# simple_motor_driver.net
KiCad netlist of a schematic drawn in Altium Designer
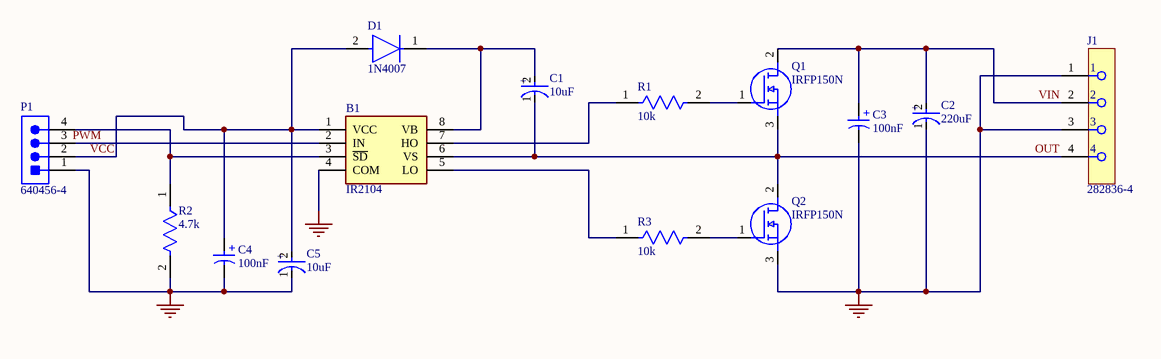
[diagram p0: simple_motor_driver.SchDoc]

(export (version "E")
  (design (tool "Eeschema 10.0.6"))
  (components
    (comp (ref "B1")
      (value "IR2104")
      (footprint "DIP762W56P254L988H533Q8N:DIP762W56P254L988H533Q8N")
      (description "Single MOSFET DRIVER, 8 Pin, Plastic, DIP")
      (libsource (lib "IR2104") (part "IR2104"))
    )
    (comp (ref "C1")
      (value "10uF")
      (footprint "FP-RAD-TH-D_16_0_5-L_25_2-MFG")
      (description "Aluminum Electrolytic Capacitors (Radial Lead Type) 47uF ±20% 400V")
      (fields (field (name "VOLTAGE") "400V") (field (name "TOLERANCE") "20%"))
      (libsource (lib "Altium Content Vault") (part "203bc49f2ac43e59fd269a8c329ed05"))
    )
    (comp (ref "C2")
      (value "220uF")
      (footprint "FP-RAD-TH-D_16_0_5-L_25_2-MFG")
      (description "Aluminum Electrolytic Capacitors (Radial Lead Type) 47uF ±20% 400V")
      (fields (field (name "VOLTAGE") "400V") (field (name "TOLERANCE") "20%"))
      (libsource (lib "Altium Content Vault") (part "203bc49f2ac43e59fd269a8c329ed05"))
    )
    (comp (ref "C3")
      (value "100nF")
      (footprint "WCAP-ATLL_D8H11.5")
      (description "860160574013 WCAP-ATLL Aluminum Electrolytic Capacitors")
      (fields (field (name "TOLERANCE") "20%"))
      (libsource (lib "Altium Content Vault") (part "Capacitor_Polarized"))
    )
    (comp (ref "C4")
      (value "100nF")
      (footprint "WCAP-ATLL_D8H11.5")
      (description "860160574013 WCAP-ATLL Aluminum Electrolytic Capacitors")
      (fields (field (name "TOLERANCE") "20%"))
      (libsource (lib "Altium Content Vault") (part "Capacitor_Polarized"))
    )
    (comp (ref "C5")
      (value "10uF")
      (footprint "FP-RAD-TH-D_16_0_5-L_25_2-MFG")
      (description "Aluminum Electrolytic Capacitors (Radial Lead Type) 47uF ±20% 400V")
      (fields (field (name "VOLTAGE") "400V") (field (name "TOLERANCE") "20%"))
      (libsource (lib "Altium Content Vault") (part "203bc49f2ac43e59fd269a8c329ed05"))
    )
    (comp (ref "D1")
      (value "1N4007")
      (footprint "FP-1N4007-MFG")
      (description "Rectifier diode 1000 V 1 A DO-41, ,")
      (fields
        (field (name "MANUFACTURER") "Diotec")
        (field (name "OCTOPART") "https://octopart.com/1n4007-diotec-4040411")
      )
      (libsource (lib "Altium Content Vault") (part "d7152d700b627762746794eb795d46e"))
    )
    (comp (ref "J1")
      (value "282836-4")
      (footprint "FP-282836-4-MFG")
      (description "282836-4 Connector, Terminal Block; Wire Receptacle; 4 Pos.; 16-30 AWG; 0.197 in. CL; Sid")
      (fields (field (name "VOLTAGE") "300V"))
      (libsource (lib "Altium Content Vault") (part "282836-4"))
    )
    (comp (ref "P1")
      (value "640456-4")
      (footprint "TECO-640456-4")
      (description "Male Header, Pitch 2.54 mm, 1 x 4 Position, Height 10.03 mm, Tail Length 3.56 mm, RoHS, Bulk")
      (fields (field (name "MANUFACTURER") "TE Connectivity"))
      (libsource (lib "Altium Content Vault") (part "CN-1P-M-R4"))
    )
    (comp (ref "Q1")
      (value "IRFP150N")
      (footprint "TO545P530X1560X2460-3P:TO545P530X1560X2460-3P")
      (description "N-channel MOSFET,IRFP150N 42A 100V")
      (libsource (lib "IRFP150N") (part "IRFP150N"))
    )
    (comp (ref "Q2")
      (value "IRFP150N")
      (footprint "TO545P530X1560X2460-3P:TO545P530X1560X2460-3P")
      (description "N-channel MOSFET,IRFP150N 42A 100V")
      (libsource (lib "IRFP150N") (part "IRFP150N"))
    )
    (comp (ref "R1")
      (value "10k")
      (footprint "FP-CF14-MFG")
      (description "RES 7.5K OHM 1/4W 5% AXIAL")
      (fields (field (name "TOLERANCE") "5%"))
      (libsource (lib "Altium Content Vault") (part "1029c3af85768c4190bb7ad29bc67b5"))
    )
    (comp (ref "R2")
      (value "4.7k")
      (footprint "FP-CF14-MFG")
      (description "RES 7.5K OHM 1/4W 5% AXIAL")
      (fields (field (name "TOLERANCE") "5%"))
      (libsource (lib "Altium Content Vault") (part "1029c3af85768c4190bb7ad29bc67b5"))
    )
    (comp (ref "R3")
      (value "10k")
      (footprint "FP-CF14-MFG")
      (description "RES 7.5K OHM 1/4W 5% AXIAL")
      (fields (field (name "TOLERANCE") "5%"))
      (libsource (lib "Altium Content Vault") (part "1029c3af85768c4190bb7ad29bc67b5"))
    )
  )
  (nets
    (net (code "1") (name "/OUT") (class "Default")
      (node (ref "B1") (pin "6") (pinfunction "VS_6") (pintype "passive"))
      (node (ref "C1") (pin "1") (pinfunction "C_1") (pintype "passive"))
      (node (ref "J1") (pin "4") (pinfunction "4_4") (pintype "passive"))
      (node (ref "Q1") (pin "3") (pinfunction "S_3") (pintype "power_in"))
      (node (ref "Q2") (pin "2") (pinfunction "D_2") (pintype "power_in"))
    )
    (net (code "2") (name "/PWM") (class "Default")
      (node (ref "B1") (pin "2") (pinfunction "IN_2") (pintype "passive"))
      (node (ref "P1") (pin "3") (pinfunction "3_3") (pintype "passive"))
    )
    (net (code "3") (name "/VCC") (class "Default")
      (node (ref "B1") (pin "1") (pinfunction "VCC_1") (pintype "passive"))
      (node (ref "C4") (pin "1") (pinfunction "P_1") (pintype "passive"))
      (node (ref "C5") (pin "2") (pinfunction "A_2") (pintype "passive"))
      (node (ref "D1") (pin "2") (pinfunction "A_2") (pintype "passive"))
      (node (ref "P1") (pin "2") (pinfunction "2_2") (pintype "passive"))
    )
    (net (code "4") (name "/VIN") (class "Default")
      (node (ref "C2") (pin "2") (pinfunction "A_2") (pintype "passive"))
      (node (ref "C3") (pin "1") (pinfunction "P_1") (pintype "passive"))
      (node (ref "J1") (pin "2") (pinfunction "2_2") (pintype "passive"))
      (node (ref "Q1") (pin "2") (pinfunction "D_2") (pintype "power_in"))
    )
    (net (code "5") (name "GND") (class "Default")
      (node (ref "B1") (pin "4") (pinfunction "COM_4") (pintype "passive"))
      (node (ref "C2") (pin "1") (pinfunction "C_1") (pintype "passive"))
      (node (ref "C3") (pin "2") (pinfunction "N_2") (pintype "passive"))
      (node (ref "C4") (pin "2") (pinfunction "N_2") (pintype "passive"))
      (node (ref "C5") (pin "1") (pinfunction "C_1") (pintype "passive"))
      (node (ref "J1") (pin "1") (pinfunction "1_1") (pintype "passive"))
      (node (ref "J1") (pin "3") (pinfunction "3_3") (pintype "passive"))
      (node (ref "P1") (pin "1") (pinfunction "1_1") (pintype "passive"))
      (node (ref "Q2") (pin "3") (pinfunction "S_3") (pintype "power_in"))
      (node (ref "R2") (pin "2") (pinfunction "2_2") (pintype "passive"))
    )
    (net (code "6") (name "Net-(B1-HO)") (class "Default")
      (node (ref "B1") (pin "7") (pinfunction "HO_7") (pintype "passive"))
      (node (ref "R1") (pin "1") (pinfunction "1_1") (pintype "passive"))
    )
    (net (code "7") (name "Net-(B1-LO)") (class "Default")
      (node (ref "B1") (pin "5") (pinfunction "LO_5") (pintype "passive"))
      (node (ref "R3") (pin "1") (pinfunction "1_1") (pintype "passive"))
    )
    (net (code "8") (name "Net-(B1-VB)") (class "Default")
      (node (ref "B1") (pin "8") (pinfunction "VB_8") (pintype "passive"))
      (node (ref "C1") (pin "2") (pinfunction "A_2") (pintype "passive"))
      (node (ref "D1") (pin "1") (pinfunction "C_1") (pintype "passive"))
    )
    (net (code "9") (name "Net-(B1-~{SD})") (class "Default")
      (node (ref "B1") (pin "3") (pinfunction "~{SD}_3") (pintype "passive"))
      (node (ref "P1") (pin "4") (pinfunction "4_4") (pintype "passive"))
      (node (ref "R2") (pin "1") (pinfunction "1_1") (pintype "passive"))
    )
    (net (code "10") (name "Net-(Q1-G)") (class "Default")
      (node (ref "Q1") (pin "1") (pinfunction "G_1") (pintype "passive"))
      (node (ref "R1") (pin "2") (pinfunction "2_2") (pintype "passive"))
    )
    (net (code "11") (name "Net-(Q2-G)") (class "Default")
      (node (ref "Q2") (pin "1") (pinfunction "G_1") (pintype "passive"))
      (node (ref "R3") (pin "2") (pinfunction "2_2") (pintype "passive"))
    )
  )
)
